# Keg_Cop_-_Sensors.net
KiCad netlist of a schematic drawn in EAGLE
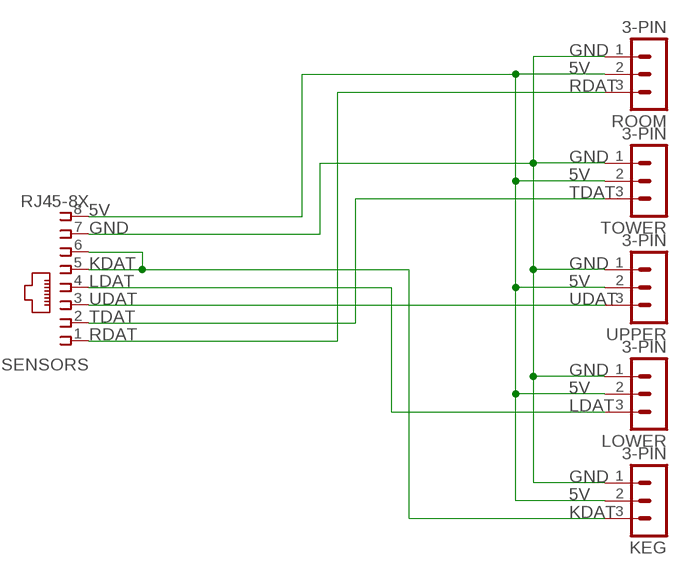
[diagram p0: schematic, sheet 1]

(export (version "E")
  (design (tool "Eeschema 10.0.6"))
  (components
    (comp (ref "KEG")
      (value "3-PIN")
      (footprint "eagle-import:HDR-3_VERT")
      (libsource (lib "eagle-import") (part "HDR-3"))
    )
    (comp (ref "LOWER")
      (value "3-PIN")
      (footprint "eagle-import:HDR-3_VERT")
      (libsource (lib "eagle-import") (part "HDR-3"))
    )
    (comp (ref "ROOM")
      (value "3-PIN")
      (footprint "eagle-import:HDR-3_VERT")
      (libsource (lib "eagle-import") (part "HDR-3"))
    )
    (comp (ref "SENSORS")
      (value "RJ45-8X")
      (footprint "eagle-import:RJ45-NO-SHIELD")
      (libsource (lib "eagle-import") (part "RJ45-8X"))
    )
    (comp (ref "TOWER")
      (value "3-PIN")
      (footprint "eagle-import:HDR-3_VERT")
      (libsource (lib "eagle-import") (part "HDR-3"))
    )
    (comp (ref "UPPER")
      (value "3-PIN")
      (footprint "eagle-import:HDR-3_VERT")
      (libsource (lib "eagle-import") (part "HDR-3"))
    )
  )
  (nets
    (net (code "1") (name "/5V") (class "Default")
      (node (ref "KEG") (pin "2") (pinfunction "2_2") (pintype "passive"))
      (node (ref "LOWER") (pin "2") (pinfunction "2_2") (pintype "passive"))
      (node (ref "ROOM") (pin "2") (pinfunction "2_2") (pintype "passive"))
      (node (ref "SENSORS") (pin "8") (pinfunction "8_8") (pintype "passive"))
      (node (ref "TOWER") (pin "2") (pinfunction "2_2") (pintype "passive"))
      (node (ref "UPPER") (pin "2") (pinfunction "2_2") (pintype "passive"))
    )
    (net (code "2") (name "/GND") (class "Default")
      (node (ref "KEG") (pin "1") (pinfunction "1_1") (pintype "passive"))
      (node (ref "LOWER") (pin "1") (pinfunction "1_1") (pintype "passive"))
      (node (ref "ROOM") (pin "1") (pinfunction "1_1") (pintype "passive"))
      (node (ref "SENSORS") (pin "7") (pinfunction "7_7") (pintype "passive"))
      (node (ref "TOWER") (pin "1") (pinfunction "1_1") (pintype "passive"))
      (node (ref "UPPER") (pin "1") (pinfunction "1_1") (pintype "passive"))
    )
    (net (code "3") (name "/KDAT") (class "Default")
      (node (ref "KEG") (pin "3") (pinfunction "3_3") (pintype "passive"))
      (node (ref "SENSORS") (pin "5") (pinfunction "5_5") (pintype "passive"))
      (node (ref "SENSORS") (pin "6") (pinfunction "6_6") (pintype "passive"))
    )
    (net (code "4") (name "/LDAT") (class "Default")
      (node (ref "LOWER") (pin "3") (pinfunction "3_3") (pintype "passive"))
      (node (ref "SENSORS") (pin "4") (pinfunction "4_4") (pintype "passive"))
    )
    (net (code "5") (name "/RDAT") (class "Default")
      (node (ref "ROOM") (pin "3") (pinfunction "3_3") (pintype "passive"))
      (node (ref "SENSORS") (pin "1") (pinfunction "1_1") (pintype "passive"))
    )
    (net (code "6") (name "/TDAT") (class "Default")
      (node (ref "SENSORS") (pin "2") (pinfunction "2_2") (pintype "passive"))
      (node (ref "TOWER") (pin "3") (pinfunction "3_3") (pintype "passive"))
    )
    (net (code "7") (name "/UDAT") (class "Default")
      (node (ref "SENSORS") (pin "3") (pinfunction "3_3") (pintype "passive"))
      (node (ref "UPPER") (pin "3") (pinfunction "3_3") (pintype "passive"))
    )
  )
)
